# Motor.net
KiCad netlist of a schematic drawn in EAGLE
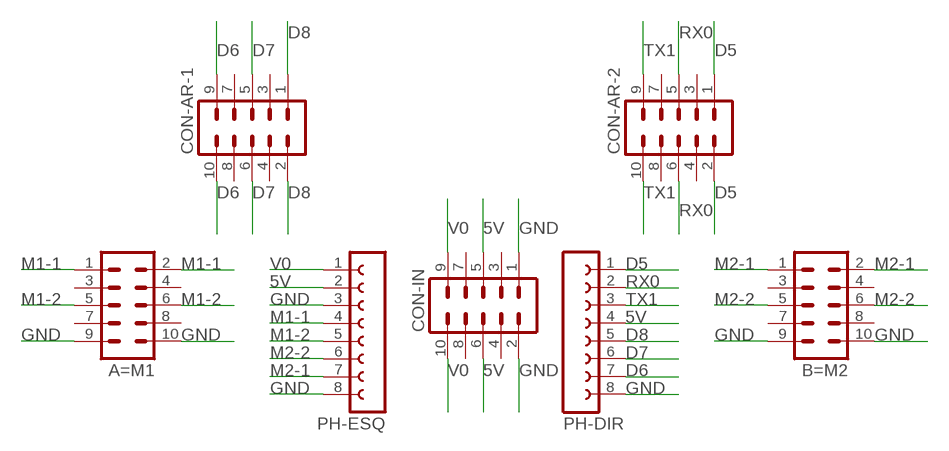
[diagram p0: schematic, sheet 1]

(export (version "E")
  (design (tool "Eeschema 10.0.6"))
  (components
    (comp (ref "A=M1")
      (value "ML10L")
      (footprint "eagle-import:ML10L")
      (libsource (lib "eagle-import") (part "ML10L"))
    )
    (comp (ref "B=M2")
      (value "ML10L")
      (footprint "eagle-import:ML10L")
      (libsource (lib "eagle-import") (part "ML10L"))
    )
    (comp (ref "CON-AR-1")
      (value "MA05-2")
      (footprint "eagle-import:MA05-2")
      (libsource (lib "eagle-import") (part "MA05-2"))
    )
    (comp (ref "CON-AR-2")
      (value "MA05-2")
      (footprint "eagle-import:MA05-2")
      (libsource (lib "eagle-import") (part "MA05-2"))
    )
    (comp (ref "CON-IN")
      (value "MA05-2")
      (footprint "eagle-import:MA05-2")
      (libsource (lib "eagle-import") (part "MA05-2"))
    )
    (comp (ref "PH-DIR")
      (value "FE08W")
      (footprint "eagle-import:FE08W")
      (libsource (lib "eagle-import") (part "FE08W"))
    )
    (comp (ref "PH-ESQ")
      (value "FE08W")
      (footprint "eagle-import:FE08W")
      (libsource (lib "eagle-import") (part "FE08W"))
    )
  )
  (nets
    (net (code "1") (name "/5V") (class "Default")
      (node (ref "CON-IN") (pin "5") (pinfunction "5_5") (pintype "passive"))
      (node (ref "CON-IN") (pin "6") (pinfunction "6_6") (pintype "passive"))
      (node (ref "PH-DIR") (pin "4") (pinfunction "4_4") (pintype "passive"))
      (node (ref "PH-ESQ") (pin "2") (pinfunction "2_2") (pintype "passive"))
    )
    (net (code "2") (name "/D5") (class "Default")
      (node (ref "CON-AR-2") (pin "1") (pinfunction "1_1") (pintype "passive"))
      (node (ref "CON-AR-2") (pin "2") (pinfunction "2_2") (pintype "passive"))
      (node (ref "PH-DIR") (pin "1") (pinfunction "1_1") (pintype "passive"))
    )
    (net (code "3") (name "/D6") (class "Default")
      (node (ref "CON-AR-1") (pin "10") (pinfunction "10_10") (pintype "passive"))
      (node (ref "CON-AR-1") (pin "9") (pinfunction "9_9") (pintype "passive"))
      (node (ref "PH-DIR") (pin "7") (pinfunction "7_7") (pintype "passive"))
    )
    (net (code "4") (name "/D7") (class "Default")
      (node (ref "CON-AR-1") (pin "5") (pinfunction "5_5") (pintype "passive"))
      (node (ref "CON-AR-1") (pin "6") (pinfunction "6_6") (pintype "passive"))
      (node (ref "PH-DIR") (pin "6") (pinfunction "6_6") (pintype "passive"))
    )
    (net (code "5") (name "/D8") (class "Default")
      (node (ref "CON-AR-1") (pin "1") (pinfunction "1_1") (pintype "passive"))
      (node (ref "CON-AR-1") (pin "2") (pinfunction "2_2") (pintype "passive"))
      (node (ref "PH-DIR") (pin "5") (pinfunction "5_5") (pintype "passive"))
    )
    (net (code "6") (name "/GND") (class "Default")
      (node (ref "A=M1") (pin "10") (pinfunction "10_10") (pintype "passive"))
      (node (ref "A=M1") (pin "9") (pinfunction "9_9") (pintype "passive"))
      (node (ref "B=M2") (pin "10") (pinfunction "10_10") (pintype "passive"))
      (node (ref "B=M2") (pin "9") (pinfunction "9_9") (pintype "passive"))
      (node (ref "CON-IN") (pin "1") (pinfunction "1_1") (pintype "passive"))
      (node (ref "CON-IN") (pin "2") (pinfunction "2_2") (pintype "passive"))
      (node (ref "PH-DIR") (pin "8") (pinfunction "8_8") (pintype "passive"))
      (node (ref "PH-ESQ") (pin "3") (pinfunction "3_3") (pintype "passive"))
      (node (ref "PH-ESQ") (pin "8") (pinfunction "8_8") (pintype "passive"))
    )
    (net (code "7") (name "/M1-1") (class "Default")
      (node (ref "A=M1") (pin "1") (pinfunction "1_1") (pintype "passive"))
      (node (ref "A=M1") (pin "2") (pinfunction "2_2") (pintype "passive"))
      (node (ref "PH-ESQ") (pin "4") (pinfunction "4_4") (pintype "passive"))
    )
    (net (code "8") (name "/M1-2") (class "Default")
      (node (ref "A=M1") (pin "5") (pinfunction "5_5") (pintype "passive"))
      (node (ref "A=M1") (pin "6") (pinfunction "6_6") (pintype "passive"))
      (node (ref "PH-ESQ") (pin "5") (pinfunction "5_5") (pintype "passive"))
    )
    (net (code "9") (name "/M2-1") (class "Default")
      (node (ref "B=M2") (pin "1") (pinfunction "1_1") (pintype "passive"))
      (node (ref "B=M2") (pin "2") (pinfunction "2_2") (pintype "passive"))
      (node (ref "PH-ESQ") (pin "7") (pinfunction "7_7") (pintype "passive"))
    )
    (net (code "10") (name "/M2-2") (class "Default")
      (node (ref "B=M2") (pin "5") (pinfunction "5_5") (pintype "passive"))
      (node (ref "B=M2") (pin "6") (pinfunction "6_6") (pintype "passive"))
      (node (ref "PH-ESQ") (pin "6") (pinfunction "6_6") (pintype "passive"))
    )
    (net (code "11") (name "/RX0") (class "Default")
      (node (ref "CON-AR-2") (pin "5") (pinfunction "5_5") (pintype "passive"))
      (node (ref "CON-AR-2") (pin "6") (pinfunction "6_6") (pintype "passive"))
      (node (ref "PH-DIR") (pin "2") (pinfunction "2_2") (pintype "passive"))
    )
    (net (code "12") (name "/TX1") (class "Default")
      (node (ref "CON-AR-2") (pin "10") (pinfunction "10_10") (pintype "passive"))
      (node (ref "CON-AR-2") (pin "9") (pinfunction "9_9") (pintype "passive"))
      (node (ref "PH-DIR") (pin "3") (pinfunction "3_3") (pintype "passive"))
    )
    (net (code "13") (name "/V0") (class "Default")
      (node (ref "CON-IN") (pin "10") (pinfunction "10_10") (pintype "passive"))
      (node (ref "CON-IN") (pin "9") (pinfunction "9_9") (pintype "passive"))
      (node (ref "PH-ESQ") (pin "1") (pinfunction "1_1") (pintype "passive"))
    )
    (net (code "14") (name "unconnected-(A=M1-Pad3)") (class "Default")
      (node (ref "A=M1") (pin "3") (pinfunction "3_3") (pintype "passive"))
    )
    (net (code "15") (name "unconnected-(A=M1-Pad4)") (class "Default")
      (node (ref "A=M1") (pin "4") (pinfunction "4_4") (pintype "passive"))
    )
    (net (code "16") (name "unconnected-(A=M1-Pad7)") (class "Default")
      (node (ref "A=M1") (pin "7") (pinfunction "7_7") (pintype "passive"))
    )
    (net (code "17") (name "unconnected-(A=M1-Pad8)") (class "Default")
      (node (ref "A=M1") (pin "8") (pinfunction "8_8") (pintype "passive"))
    )
    (net (code "18") (name "unconnected-(B=M2-Pad3)") (class "Default")
      (node (ref "B=M2") (pin "3") (pinfunction "3_3") (pintype "passive"))
    )
    (net (code "19") (name "unconnected-(B=M2-Pad4)") (class "Default")
      (node (ref "B=M2") (pin "4") (pinfunction "4_4") (pintype "passive"))
    )
    (net (code "20") (name "unconnected-(B=M2-Pad7)") (class "Default")
      (node (ref "B=M2") (pin "7") (pinfunction "7_7") (pintype "passive"))
    )
    (net (code "21") (name "unconnected-(B=M2-Pad8)") (class "Default")
      (node (ref "B=M2") (pin "8") (pinfunction "8_8") (pintype "passive"))
    )
    (net (code "22") (name "unconnected-(CON-AR-1-Pad3)") (class "Default")
      (node (ref "CON-AR-1") (pin "3") (pinfunction "3_3") (pintype "passive"))
    )
    (net (code "23") (name "unconnected-(CON-AR-1-Pad4)") (class "Default")
      (node (ref "CON-AR-1") (pin "4") (pinfunction "4_4") (pintype "passive"))
    )
    (net (code "24") (name "unconnected-(CON-AR-1-Pad7)") (class "Default")
      (node (ref "CON-AR-1") (pin "7") (pinfunction "7_7") (pintype "passive"))
    )
    (net (code "25") (name "unconnected-(CON-AR-1-Pad8)") (class "Default")
      (node (ref "CON-AR-1") (pin "8") (pinfunction "8_8") (pintype "passive"))
    )
    (net (code "26") (name "unconnected-(CON-AR-2-Pad3)") (class "Default")
      (node (ref "CON-AR-2") (pin "3") (pinfunction "3_3") (pintype "passive"))
    )
    (net (code "27") (name "unconnected-(CON-AR-2-Pad4)") (class "Default")
      (node (ref "CON-AR-2") (pin "4") (pinfunction "4_4") (pintype "passive"))
    )
    (net (code "28") (name "unconnected-(CON-AR-2-Pad7)") (class "Default")
      (node (ref "CON-AR-2") (pin "7") (pinfunction "7_7") (pintype "passive"))
    )
    (net (code "29") (name "unconnected-(CON-AR-2-Pad8)") (class "Default")
      (node (ref "CON-AR-2") (pin "8") (pinfunction "8_8") (pintype "passive"))
    )
    (net (code "30") (name "unconnected-(CON-IN-Pad3)") (class "Default")
      (node (ref "CON-IN") (pin "3") (pinfunction "3_3") (pintype "passive"))
    )
    (net (code "31") (name "unconnected-(CON-IN-Pad4)") (class "Default")
      (node (ref "CON-IN") (pin "4") (pinfunction "4_4") (pintype "passive"))
    )
    (net (code "32") (name "unconnected-(CON-IN-Pad7)") (class "Default")
      (node (ref "CON-IN") (pin "7") (pinfunction "7_7") (pintype "passive"))
    )
    (net (code "33") (name "unconnected-(CON-IN-Pad8)") (class "Default")
      (node (ref "CON-IN") (pin "8") (pinfunction "8_8") (pintype "passive"))
    )
  )
)
